# Power.net
KiCad netlist of a schematic drawn in Altium Designer
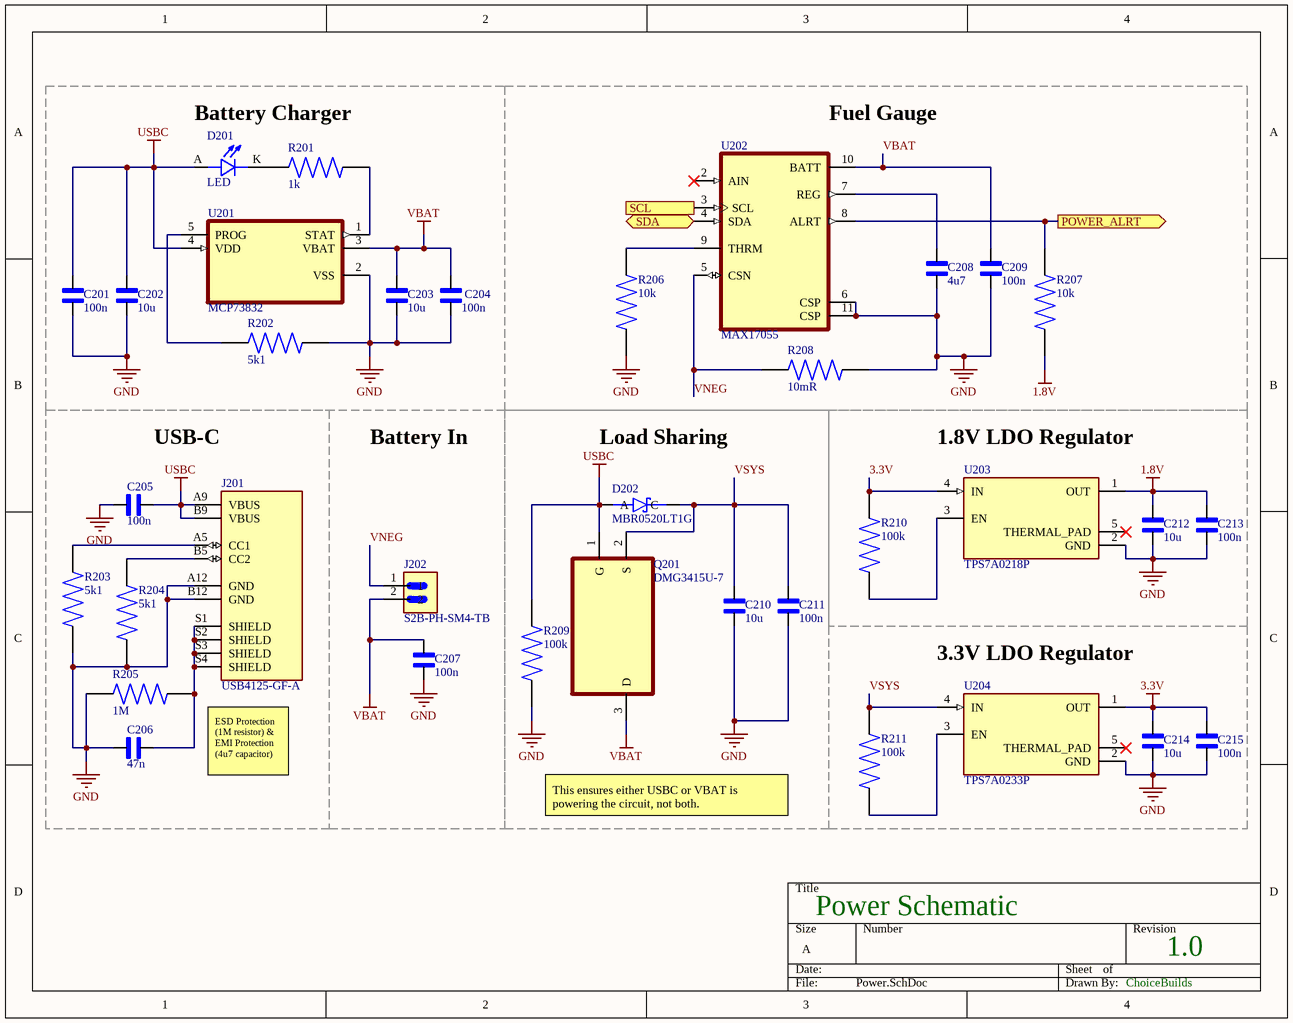
[diagram p0: Power.SchDoc]

(export (version "E")
  (design (tool "Eeschema 10.0.6"))
  (components
    (comp (ref "C201") (value "100n") (footprint "0402c") (libsource (lib "UbiWatch_SchLib") (part "0402c")))
    (comp (ref "C202") (value "10u") (footprint "0603c") (libsource (lib "UbiWatch_SchLib") (part "0603c")))
    (comp (ref "C203") (value "10u") (footprint "0603c") (libsource (lib "") (part "0603c_1")))
    (comp (ref "C204") (value "100n") (footprint "0402c") (libsource (lib "UbiWatch_SchLib") (part "0402c")))
    (comp (ref "C205") (value "100n") (footprint "0402c") (libsource (lib "") (part "0402c_1")))
    (comp (ref "C206") (value "47n") (footprint "0402c") (libsource (lib "") (part "0402c_1")))
    (comp (ref "C207") (value "100n") (footprint "0402c") (libsource (lib "") (part "0402c_2")))
    (comp (ref "C208") (value "4u7") (footprint "0603c") (libsource (lib "UbiWatch_SchLib") (part "0603c")))
    (comp (ref "C209") (value "100n") (footprint "0402c") (libsource (lib "UbiWatch_SchLib") (part "0402c")))
    (comp (ref "C210") (value "10u") (footprint "0603c") (libsource (lib "UbiWatch_SchLib") (part "0603c")))
    (comp (ref "C211") (value "100n") (footprint "0402c") (libsource (lib "UbiWatch_SchLib") (part "0402c")))
    (comp (ref "C212") (value "10u") (footprint "0603c") (libsource (lib "UbiWatch_SchLib") (part "0603c")))
    (comp (ref "C213") (value "100n") (footprint "0402c") (libsource (lib "UbiWatch_SchLib") (part "0402c")))
    (comp (ref "C214") (value "10u") (footprint "0603c") (libsource (lib "UbiWatch_SchLib") (part "0603c")))
    (comp (ref "C215") (value "100n") (footprint "0402c") (libsource (lib "UbiWatch_SchLib") (part "0402c")))
    (comp (ref "D201") (value "LED") (footprint ".LED") (libsource (lib "UbiWatch_SchLib") (part ".LED")))
    (comp (ref "D202")
      (value "MBR0520LT1G")
      (footprint "MBR0520LT1G")
      (libsource (lib "UbiWatch_SchLib") (part "MBR0520LT1G"))
    )
    (comp (ref "J201")
      (value "USB4125-GF-A")
      (footprint "USB4125-GF-A")
      (libsource (lib "JWatch_SchLib") (part "USB4125-GF-A"))
    )
    (comp (ref "J202")
      (value "S2B-PH-SM4-TB")
      (footprint "S2B-PH-SM4-TB")
      (libsource (lib "UbiWatch_SchLib") (part "S2B-PH-SM4-TB"))
    )
    (comp (ref "Q201")
      (value "DMG3415U-7")
      (footprint "DMG3415U-7")
      (libsource (lib "UbiWatch_SchLib") (part "DMG3415U-7"))
    )
    (comp (ref "R201") (value "1k") (footprint "0402r") (libsource (lib "UbiWatch_SchLib") (part "0402r")))
    (comp (ref "R202") (value "5k1") (footprint "0402r") (libsource (lib "UbiWatch_SchLib") (part "0402r")))
    (comp (ref "R203") (value "5k1") (footprint "0402r") (libsource (lib "UbiWatch_SchLib") (part "0402r")))
    (comp (ref "R204") (value "5k1") (footprint "0402r") (libsource (lib "UbiWatch_SchLib") (part "0402r")))
    (comp (ref "R205") (value "1M") (footprint "0402r") (libsource (lib "UbiWatch_SchLib") (part "0402r")))
    (comp (ref "R206") (value "10k") (footprint "0402r") (libsource (lib "UbiWatch_SchLib") (part "0402r")))
    (comp (ref "R207") (value "10k") (footprint "0402r") (libsource (lib "UbiWatch_SchLib") (part "0402r")))
    (comp (ref "R208") (value "10mR") (footprint "0805r") (libsource (lib "UbiWatch_SchLib") (part "0805r")))
    (comp (ref "R209") (value "100k") (footprint "0402r") (libsource (lib "UbiWatch_SchLib") (part "0402r")))
    (comp (ref "R210") (value "100k") (footprint "0402r") (libsource (lib "UbiWatch_SchLib") (part "0402r")))
    (comp (ref "R211") (value "100k") (footprint "0402r") (libsource (lib "UbiWatch_SchLib") (part "0402r")))
    (comp (ref "U201")
      (value "MCP73832")
      (footprint "MCP73832")
      (libsource (lib "JWatch_SchLib") (part "MCP73832"))
    )
    (comp (ref "U202")
      (value "MAX17055")
      (footprint "MAX17055")
      (libsource (lib "JWatch_SchLib") (part "MAX17055"))
    )
    (comp (ref "U203")
      (value "TPS7A0218P")
      (footprint "TPS7A0218P")
      (libsource (lib "JWatch_SchLib") (part "TPS7A0218P"))
    )
    (comp (ref "U204")
      (value "TPS7A0233P")
      (footprint "TPS7A0233P")
      (libsource (lib "JWatch_SchLib") (part "TPS7A0233P"))
    )
  )
  (nets
    (net (code "1") (name "/POWER_ALRT") (class "Default")
      (node (ref "R207") (pin "2") (pinfunction "2_2") (pintype "passive"))
      (node (ref "U202") (pin "8") (pinfunction "ALRT_8") (pintype "output"))
    )
    (net (code "2") (name "/SCL") (class "Default")
      (node (ref "U202") (pin "3") (pinfunction "SCL_3") (pintype "input"))
    )
    (net (code "3") (name "/SDA") (class "Default")
      (node (ref "U202") (pin "4") (pinfunction "SDA_4") (pintype "input"))
    )
    (net (code "4") (name "/VNEG") (class "Default")
      (node (ref "J202") (pin "1") (pinfunction "1_1") (pintype "passive"))
      (node (ref "R208") (pin "1") (pinfunction "1_1") (pintype "passive"))
      (node (ref "U202") (pin "5") (pinfunction "CSN_5") (pintype "bidirectional"))
    )
    (net (code "5") (name "/VSYS") (class "Default")
      (node (ref "C210") (pin "2") (pinfunction "2_2") (pintype "passive"))
      (node (ref "C211") (pin "2") (pinfunction "2_2") (pintype "passive"))
      (node (ref "D202") (pin "C") (pinfunction "C_C") (pintype "passive"))
      (node (ref "Q201") (pin "2") (pinfunction "S_2") (pintype "power_in"))
      (node (ref "R211") (pin "2") (pinfunction "2_2") (pintype "passive"))
      (node (ref "U204") (pin "4") (pinfunction "IN_4") (pintype "input"))
    )
    (net (code "6") (name "1.8V") (class "Default")
      (node (ref "C212") (pin "2") (pinfunction "2_2") (pintype "passive"))
      (node (ref "C213") (pin "2") (pinfunction "2_2") (pintype "passive"))
      (node (ref "R207") (pin "1") (pinfunction "1_1") (pintype "passive"))
      (node (ref "U203") (pin "1") (pinfunction "OUT_1") (pintype "power_in"))
    )
    (net (code "7") (name "3.3V") (class "Default")
      (node (ref "C214") (pin "2") (pinfunction "2_2") (pintype "passive"))
      (node (ref "C215") (pin "2") (pinfunction "2_2") (pintype "passive"))
      (node (ref "R210") (pin "2") (pinfunction "2_2") (pintype "passive"))
      (node (ref "U203") (pin "4") (pinfunction "IN_4") (pintype "input"))
      (node (ref "U204") (pin "1") (pinfunction "OUT_1") (pintype "power_in"))
    )
    (net (code "8") (name "GND") (class "Default")
      (node (ref "C201") (pin "1") (pinfunction "1_1") (pintype "passive"))
      (node (ref "C202") (pin "1") (pinfunction "1_1") (pintype "passive"))
      (node (ref "C203") (pin "1") (pinfunction "1_1") (pintype "passive"))
      (node (ref "C204") (pin "1") (pinfunction "1_1") (pintype "passive"))
      (node (ref "C205") (pin "1") (pinfunction "1_1") (pintype "passive"))
      (node (ref "C206") (pin "1") (pinfunction "1_1") (pintype "passive"))
      (node (ref "C207") (pin "2") (pinfunction "2_2") (pintype "passive"))
      (node (ref "C208") (pin "1") (pinfunction "1_1") (pintype "passive"))
      (node (ref "C209") (pin "1") (pinfunction "1_1") (pintype "passive"))
      (node (ref "C210") (pin "1") (pinfunction "1_1") (pintype "passive"))
      (node (ref "C211") (pin "1") (pinfunction "1_1") (pintype "passive"))
      (node (ref "C212") (pin "1") (pinfunction "1_1") (pintype "passive"))
      (node (ref "C213") (pin "1") (pinfunction "1_1") (pintype "passive"))
      (node (ref "C214") (pin "1") (pinfunction "1_1") (pintype "passive"))
      (node (ref "C215") (pin "1") (pinfunction "1_1") (pintype "passive"))
      (node (ref "J201") (pin "A12") (pinfunction "GND_A12") (pintype "power_in"))
      (node (ref "J201") (pin "B12") (pinfunction "GND_B12") (pintype "power_in"))
      (node (ref "R202") (pin "2") (pinfunction "2_2") (pintype "passive"))
      (node (ref "R203") (pin "1") (pinfunction "1_1") (pintype "passive"))
      (node (ref "R204") (pin "1") (pinfunction "1_1") (pintype "passive"))
      (node (ref "R205") (pin "1") (pinfunction "1_1") (pintype "passive"))
      (node (ref "R206") (pin "1") (pinfunction "1_1") (pintype "passive"))
      (node (ref "R208") (pin "2") (pinfunction "2_2") (pintype "passive"))
      (node (ref "R209") (pin "1") (pinfunction "1_1") (pintype "passive"))
      (node (ref "U201") (pin "2") (pinfunction "VSS_2") (pintype "power_in"))
      (node (ref "U202") (pin "11") (pinfunction "CSP_11") (pintype "power_in"))
      (node (ref "U202") (pin "6") (pinfunction "CSP_6") (pintype "power_in"))
      (node (ref "U203") (pin "2") (pinfunction "GND_2") (pintype "power_in"))
      (node (ref "U204") (pin "2") (pinfunction "GND_2") (pintype "power_in"))
    )
    (net (code "9") (name "Net-(C206-Pad2)") (class "Default")
      (node (ref "C206") (pin "2") (pinfunction "2_2") (pintype "passive"))
      (node (ref "J201") (pin "S1") (pinfunction "SHIELD_S1") (pintype "passive"))
      (node (ref "J201") (pin "S2") (pinfunction "SHIELD_S2") (pintype "passive"))
      (node (ref "J201") (pin "S3") (pinfunction "SHIELD_S3") (pintype "passive"))
      (node (ref "J201") (pin "S4") (pinfunction "SHIELD_S4") (pintype "passive"))
      (node (ref "R205") (pin "2") (pinfunction "2_2") (pintype "passive"))
    )
    (net (code "10") (name "Net-(D201-PadK)") (class "Default")
      (node (ref "D201") (pin "K") (pinfunction "K_K") (pintype "passive"))
      (node (ref "R201") (pin "1") (pinfunction "1_1") (pintype "passive"))
    )
    (net (code "11") (name "Net-(J201-CC1)") (class "Default")
      (node (ref "J201") (pin "A5") (pinfunction "CC1_A5") (pintype "bidirectional"))
      (node (ref "R203") (pin "2") (pinfunction "2_2") (pintype "passive"))
    )
    (net (code "12") (name "Net-(J201-CC2)") (class "Default")
      (node (ref "J201") (pin "B5") (pinfunction "CC2_B5") (pintype "bidirectional"))
      (node (ref "R204") (pin "2") (pinfunction "2_2") (pintype "passive"))
    )
    (net (code "13") (name "Net-(U201-PROG)") (class "Default")
      (node (ref "R202") (pin "1") (pinfunction "1_1") (pintype "passive"))
      (node (ref "U201") (pin "5") (pinfunction "PROG_5") (pintype "passive"))
    )
    (net (code "14") (name "Net-(U201-STAT)") (class "Default")
      (node (ref "R201") (pin "2") (pinfunction "2_2") (pintype "passive"))
      (node (ref "U201") (pin "1") (pinfunction "STAT_1") (pintype "output"))
    )
    (net (code "15") (name "Net-(U202-REG)") (class "Default")
      (node (ref "C208") (pin "2") (pinfunction "2_2") (pintype "passive"))
      (node (ref "U202") (pin "7") (pinfunction "REG_7") (pintype "output"))
    )
    (net (code "16") (name "Net-(U202-THRM)") (class "Default")
      (node (ref "R206") (pin "2") (pinfunction "2_2") (pintype "passive"))
      (node (ref "U202") (pin "9") (pinfunction "THRM_9") (pintype "passive"))
    )
    (net (code "17") (name "Net-(U203-EN)") (class "Default")
      (node (ref "R210") (pin "1") (pinfunction "1_1") (pintype "passive"))
      (node (ref "U203") (pin "3") (pinfunction "EN_3") (pintype "passive"))
    )
    (net (code "18") (name "Net-(U204-EN)") (class "Default")
      (node (ref "R211") (pin "1") (pinfunction "1_1") (pintype "passive"))
      (node (ref "U204") (pin "3") (pinfunction "EN_3") (pintype "passive"))
    )
    (net (code "19") (name "USBC") (class "Default")
      (node (ref "C201") (pin "2") (pinfunction "2_2") (pintype "passive"))
      (node (ref "C202") (pin "2") (pinfunction "2_2") (pintype "passive"))
      (node (ref "C205") (pin "2") (pinfunction "2_2") (pintype "passive"))
      (node (ref "D201") (pin "A") (pinfunction "A_A") (pintype "passive"))
      (node (ref "D202") (pin "A") (pinfunction "A_A") (pintype "passive"))
      (node (ref "J201") (pin "A9") (pinfunction "VBUS_A9") (pintype "power_in"))
      (node (ref "J201") (pin "B9") (pinfunction "VBUS_B9") (pintype "power_in"))
      (node (ref "Q201") (pin "1") (pinfunction "G_1") (pintype "power_in"))
      (node (ref "R209") (pin "2") (pinfunction "2_2") (pintype "passive"))
      (node (ref "U201") (pin "4") (pinfunction "VDD_4") (pintype "input"))
    )
    (net (code "20") (name "VBAT") (class "Default")
      (node (ref "C203") (pin "2") (pinfunction "2_2") (pintype "passive"))
      (node (ref "C204") (pin "2") (pinfunction "2_2") (pintype "passive"))
      (node (ref "C207") (pin "1") (pinfunction "1_1") (pintype "passive"))
      (node (ref "C209") (pin "2") (pinfunction "2_2") (pintype "passive"))
      (node (ref "J202") (pin "2") (pinfunction "2_2") (pintype "passive"))
      (node (ref "Q201") (pin "3") (pinfunction "D_3") (pintype "power_in"))
      (node (ref "U201") (pin "3") (pinfunction "VBAT_3") (pintype "power_in"))
      (node (ref "U202") (pin "10") (pinfunction "BATT_10") (pintype "power_in"))
    )
    (net (code "21") (name "unconnected-(U202-AIN-Pad2)") (class "Default")
      (node (ref "U202") (pin "2") (pinfunction "AIN_2") (pintype "input+no_connect"))
    )
    (net (code "22") (name "unconnected-(U203-THERMAL_PAD-Pad5)") (class "Default")
      (node (ref "U203") (pin "5") (pinfunction "THERMAL_PAD_5") (pintype "power_in+no_connect"))
    )
    (net (code "23") (name "unconnected-(U204-THERMAL_PAD-Pad5)") (class "Default")
      (node (ref "U204") (pin "5") (pinfunction "THERMAL_PAD_5") (pintype "power_in+no_connect"))
    )
  )
)
